# grizzly_bear.net
KiCad netlist of a schematic drawn in EAGLE
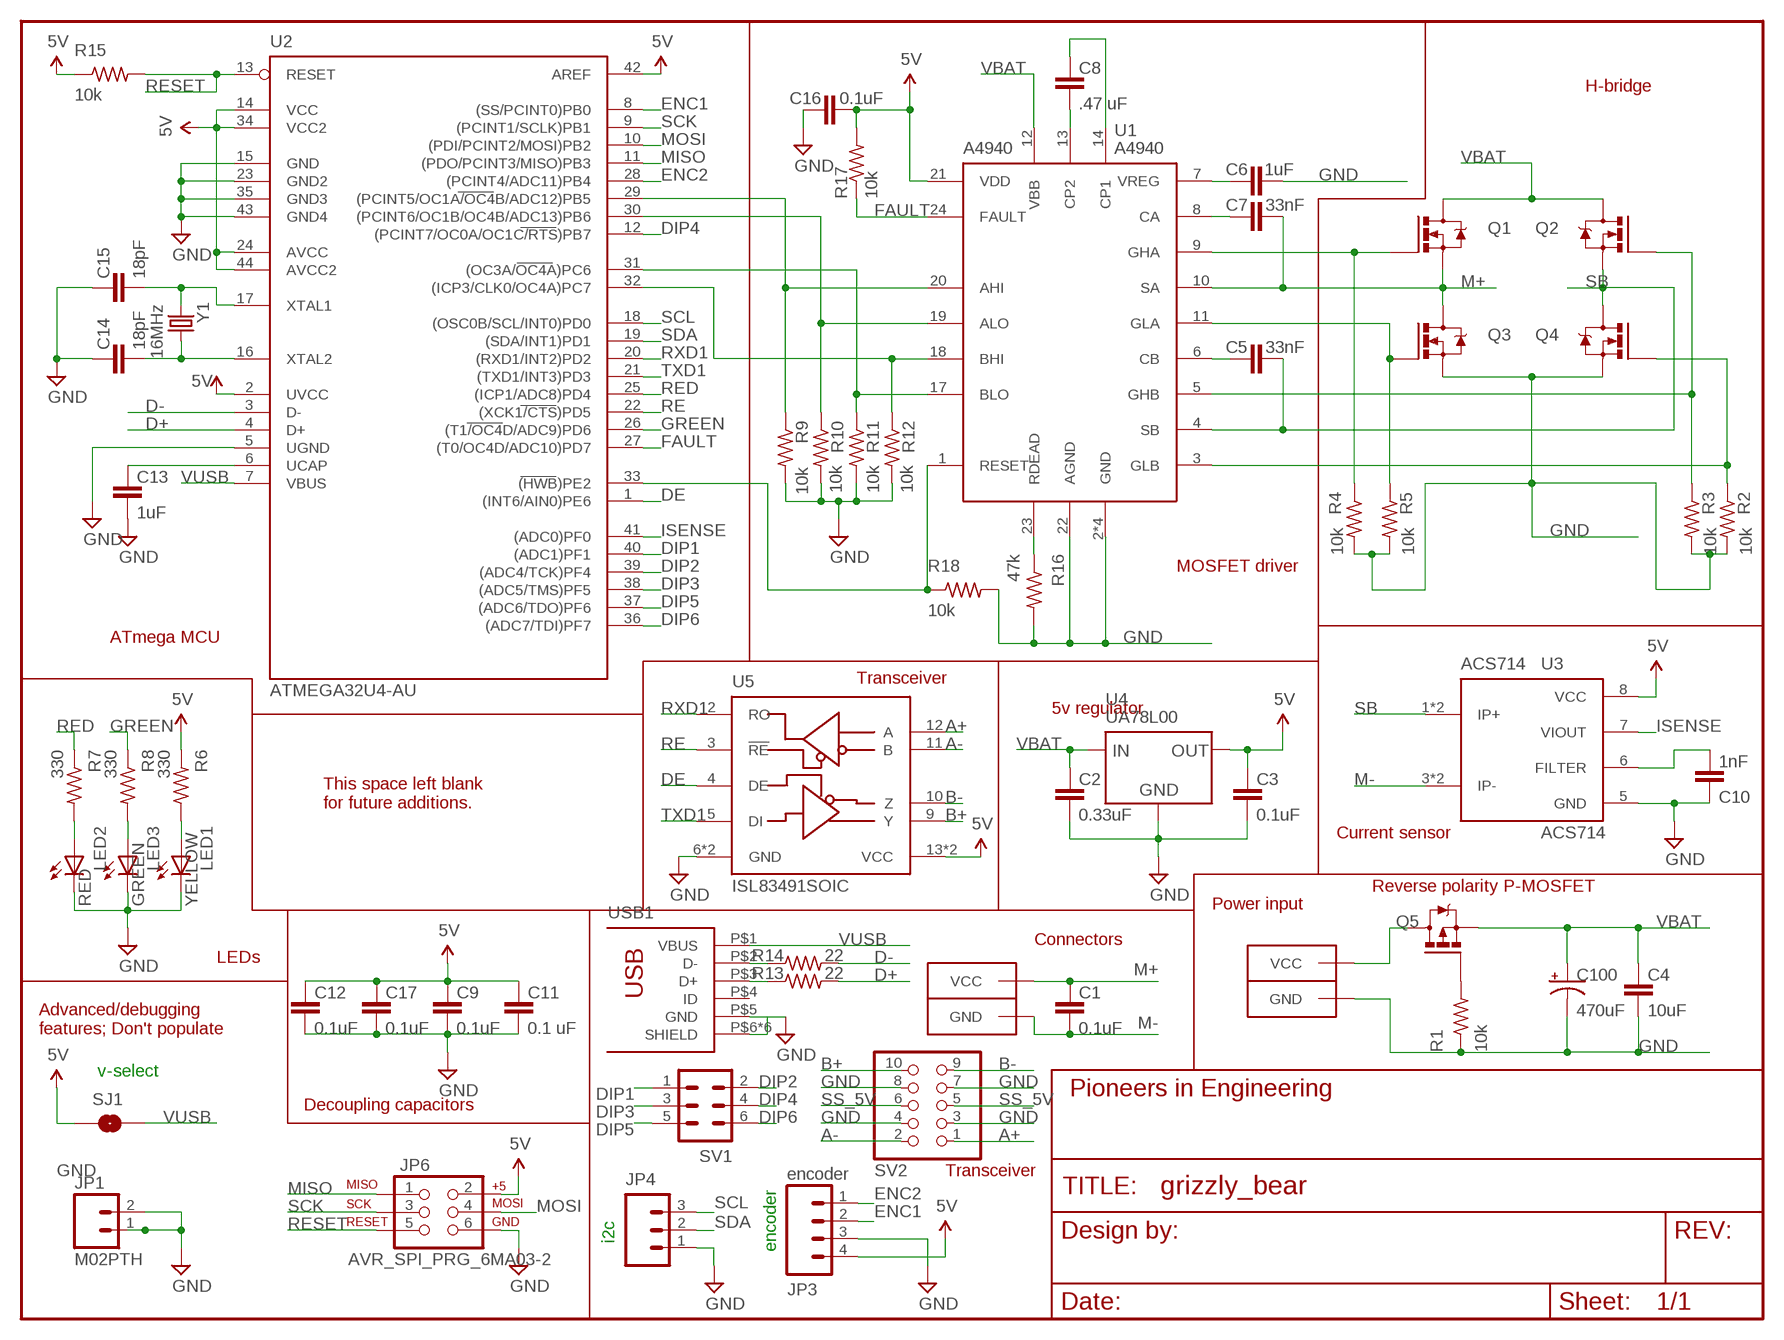
[diagram p0: schematic, sheet 1]

(export (version "E")
  (design (tool "Eeschema 10.0.6"))
  (components
    (comp (ref "C1")
      (value "0.1uF")
      (footprint "eagle-import:0603-CAP")
      (libsource (lib "eagle-import") (part "CAP0603-CAP"))
    )
    (comp (ref "C2")
      (value "0.33uF")
      (footprint "eagle-import:0603-CAP")
      (libsource (lib "eagle-import") (part "CAP0603-CAP"))
    )
    (comp (ref "C3")
      (value "0.1uF")
      (footprint "eagle-import:0603-CAP")
      (libsource (lib "eagle-import") (part "CAP0603-CAP"))
    )
    (comp (ref "C4")
      (value "10uF")
      (footprint "eagle-import:1206")
      (libsource (lib "eagle-import") (part "CAP1206"))
    )
    (comp (ref "C5")
      (value "33nF")
      (footprint "eagle-import:0603-CAP")
      (libsource (lib "eagle-import") (part "CAP0603-CAP"))
    )
    (comp (ref "C6")
      (value "1uF")
      (footprint "eagle-import:0603-CAP")
      (libsource (lib "eagle-import") (part "CAP0603-CAP"))
    )
    (comp (ref "C7")
      (value "33nF")
      (footprint "eagle-import:0603-CAP")
      (libsource (lib "eagle-import") (part "CAP0603-CAP"))
    )
    (comp (ref "C8")
      (value ".47 uF")
      (footprint "eagle-import:0603-CAP")
      (libsource (lib "eagle-import") (part "CAP0603-CAP"))
    )
    (comp (ref "C9")
      (value "0.1uF")
      (footprint "eagle-import:0603-CAP")
      (libsource (lib "eagle-import") (part "CAP0603-CAP"))
    )
    (comp (ref "C10")
      (value "1nF")
      (footprint "eagle-import:0603-CAP")
      (libsource (lib "eagle-import") (part "CAP0603-CAP"))
    )
    (comp (ref "C11")
      (value "0.1 uF")
      (footprint "eagle-import:0603-CAP")
      (libsource (lib "eagle-import") (part "CAP0603-CAP"))
    )
    (comp (ref "C12")
      (value "0.1uF")
      (footprint "eagle-import:0603-CAP")
      (libsource (lib "eagle-import") (part "CAP0603-CAP"))
    )
    (comp (ref "C13")
      (value "1uF")
      (footprint "eagle-import:0603-CAP")
      (libsource (lib "eagle-import") (part "CAP0603-CAP"))
    )
    (comp (ref "C14")
      (value "18pF")
      (footprint "eagle-import:0603-CAP")
      (libsource (lib "eagle-import") (part "CAP0603-CAP"))
    )
    (comp (ref "C15")
      (value "18pF")
      (footprint "eagle-import:0603-CAP")
      (libsource (lib "eagle-import") (part "CAP0603-CAP"))
    )
    (comp (ref "C16")
      (value "0.1uF")
      (footprint "eagle-import:0603-CAP")
      (libsource (lib "eagle-import") (part "CAP0603-CAP"))
    )
    (comp (ref "C17")
      (value "0.1uF")
      (footprint "eagle-import:0603-CAP")
      (libsource (lib "eagle-import") (part "CAP0603-CAP"))
    )
    (comp (ref "C100")
      (value "470uF")
      (footprint "eagle-import:PANASONIC_G")
      (libsource (lib "eagle-import") (part "CAP_POLG"))
    )
    (comp (ref "JP1")
      (value "M02PTH")
      (footprint "eagle-import:1X02")
      (libsource (lib "eagle-import") (part "M02PTH"))
    )
    (comp (ref "JP3")
      (value "encoder")
      (footprint "eagle-import:1X04-MTA")
      (libsource (lib "eagle-import") (part "M041X04-MTA"))
    )
    (comp (ref "JP4")
      (value "M031X03-MTA")
      (footprint "eagle-import:1X03-MTA")
      (libsource (lib "eagle-import") (part "M031X03-MTA"))
    )
    (comp (ref "JP6")
      (value "AVR_SPI_PRG_6MA03-2")
      (footprint "eagle-import:MA03-2")
      (libsource (lib "eagle-import") (part "AVR_SPI_PRG_6MA03-2"))
    )
    (comp (ref "LED1")
      (value "YELLOW")
      (footprint "eagle-import:LED-0805")
      (libsource (lib "eagle-import") (part "LED0805"))
    )
    (comp (ref "LED2")
      (value "RED")
      (footprint "eagle-import:LED-0805")
      (libsource (lib "eagle-import") (part "LED0805"))
    )
    (comp (ref "LED3")
      (value "GREEN")
      (footprint "eagle-import:LED-0805")
      (libsource (lib "eagle-import") (part "LED0805"))
    )
    (comp (ref "Q1")
      (value "PSMN4R0")
      (footprint "eagle-import:SOT669")
      (libsource (lib "eagle-import") (part "N-CHANNEL-MOSFETSOT669"))
    )
    (comp (ref "Q2")
      (value "PSMN4R0")
      (footprint "eagle-import:SOT669")
      (libsource (lib "eagle-import") (part "N-CHANNEL-MOSFETSOT669"))
    )
    (comp (ref "Q3")
      (value "PSMN4R0")
      (footprint "eagle-import:SOT669")
      (libsource (lib "eagle-import") (part "N-CHANNEL-MOSFETSOT669"))
    )
    (comp (ref "Q4")
      (value "PSMN4R0")
      (footprint "eagle-import:SOT669")
      (libsource (lib "eagle-import") (part "N-CHANNEL-MOSFETSOT669"))
    )
    (comp (ref "Q5")
      (value "IPD90P03P4L")
      (footprint "eagle-import:TO252")
      (libsource (lib "eagle-import") (part "P-CHANNEL-MOSFETTO252"))
    )
    (comp (ref "R1")
      (value "10k")
      (footprint "eagle-import:R0603")
      (libsource (lib "eagle-import") (part "R-US_R0603"))
    )
    (comp (ref "R2")
      (value "10k")
      (footprint "eagle-import:R0603")
      (libsource (lib "eagle-import") (part "R-US_R0603"))
    )
    (comp (ref "R3")
      (value "10k")
      (footprint "eagle-import:R0603")
      (libsource (lib "eagle-import") (part "R-US_R0603"))
    )
    (comp (ref "R4")
      (value "10k")
      (footprint "eagle-import:R0603")
      (libsource (lib "eagle-import") (part "R-US_R0603"))
    )
    (comp (ref "R5")
      (value "10k")
      (footprint "eagle-import:R0603")
      (libsource (lib "eagle-import") (part "R-US_R0603"))
    )
    (comp (ref "R6")
      (value "330")
      (footprint "eagle-import:R0603")
      (libsource (lib "eagle-import") (part "R-US_R0603"))
    )
    (comp (ref "R7")
      (value "330")
      (footprint "eagle-import:R0603")
      (libsource (lib "eagle-import") (part "R-US_R0603"))
    )
    (comp (ref "R8")
      (value "330")
      (footprint "eagle-import:R0603")
      (libsource (lib "eagle-import") (part "R-US_R0603"))
    )
    (comp (ref "R9")
      (value "10k")
      (footprint "eagle-import:R0603")
      (libsource (lib "eagle-import") (part "R-US_R0603"))
    )
    (comp (ref "R10")
      (value "10k")
      (footprint "eagle-import:R0603")
      (libsource (lib "eagle-import") (part "R-US_R0603"))
    )
    (comp (ref "R11")
      (value "10k")
      (footprint "eagle-import:R0603")
      (libsource (lib "eagle-import") (part "R-US_R0603"))
    )
    (comp (ref "R12")
      (value "10k")
      (footprint "eagle-import:R0603")
      (libsource (lib "eagle-import") (part "R-US_R0603"))
    )
    (comp (ref "R13")
      (value "22")
      (footprint "eagle-import:R0603")
      (libsource (lib "eagle-import") (part "R-US_R0603"))
    )
    (comp (ref "R14")
      (value "22")
      (footprint "eagle-import:R0603")
      (libsource (lib "eagle-import") (part "R-US_R0603"))
    )
    (comp (ref "R15")
      (value "10k")
      (footprint "eagle-import:R0603")
      (libsource (lib "eagle-import") (part "R-US_R0603"))
    )
    (comp (ref "R16")
      (value "47k")
      (footprint "eagle-import:R0603")
      (libsource (lib "eagle-import") (part "R-US_R0603"))
    )
    (comp (ref "R17")
      (value "10k")
      (footprint "eagle-import:R0603")
      (libsource (lib "eagle-import") (part "R-US_R0603"))
    )
    (comp (ref "R18")
      (value "10k")
      (footprint "eagle-import:R0603")
      (libsource (lib "eagle-import") (part "R-US_R0603"))
    )
    (comp (ref "SJ1")
      (value "SOLDERJUMPERNO")
      (footprint "eagle-import:SJ_2S-NO")
      (libsource (lib "eagle-import") (part "SOLDERJUMPERNO"))
    )
    (comp (ref "SV1")
      (value "MA03-2")
      (footprint "eagle-import:MA03-2")
      (libsource (lib "eagle-import") (part "MA03-2"))
    )
    (comp (ref "SV2")
      (value "SENSOR_CON_5PINPTH-SHROUDED")
      (footprint "eagle-import:2X5_SHROUDED")
      (libsource (lib "eagle-import") (part "SENSOR_CON_5PINPTH-SHROUDED"))
    )
    (comp (ref "U$18")
      (value "ANDERSONVERTICAL")
      (footprint "eagle-import:ANDERSON_VERTICAL")
      (libsource (lib "eagle-import") (part "ANDERSONVERTICAL"))
    )
    (comp (ref "U$19")
      (value "ANDERSONVERTICAL")
      (footprint "eagle-import:ANDERSON_VERTICAL")
      (libsource (lib "eagle-import") (part "ANDERSONVERTICAL"))
    )
    (comp (ref "U1")
      (value "A4940")
      (footprint "eagle-import:24-PIN_TSSOP")
      (libsource (lib "eagle-import") (part "A4940"))
    )
    (comp (ref "U2")
      (value "ATMEGA32U4-AU")
      (footprint "eagle-import:TQFP44")
      (libsource (lib "eagle-import") (part "ATMEGA32U4-AU"))
    )
    (comp (ref "U3")
      (value "ACS714")
      (footprint "eagle-import:8-PIN_SOIC")
      (libsource (lib "eagle-import") (part "ACS714"))
    )
    (comp (ref "U4")
      (value "UA78L00")
      (footprint "eagle-import:SOT-89-3")
      (libsource (lib "eagle-import") (part "UA78L00"))
    )
    (comp (ref "U5")
      (value "ISL83491SOIC")
      (footprint "eagle-import:SOIC14")
      (libsource (lib "eagle-import") (part "ISL83491SOIC"))
    )
    (comp (ref "USB1")
      (value "USB-OTGMICRO-AB")
      (footprint "eagle-import:USB-MICRO-AB")
      (libsource (lib "eagle-import") (part "USB-OTGMICRO-AB"))
    )
    (comp (ref "Y1")
      (value "16MHz")
      (footprint "eagle-import:HC49UP")
      (libsource (lib "eagle-import") (part "CRYSTALSMD"))
    )
  )
  (nets
    (net (code "1") (name "/A+") (class "Default")
      (node (ref "SV2") (pin "1") (pinfunction "1_1") (pintype "passive"))
      (node (ref "U5") (pin "12") (pinfunction "A_12") (pintype "bidirectional"))
    )
    (net (code "2") (name "/A-") (class "Default")
      (node (ref "SV2") (pin "2") (pinfunction "2_2") (pintype "passive"))
      (node (ref "U5") (pin "11") (pinfunction "B_11") (pintype "bidirectional"))
    )
    (net (code "3") (name "/B+") (class "Default")
      (node (ref "SV2") (pin "10") (pinfunction "10_10") (pintype "passive"))
      (node (ref "U5") (pin "9") (pinfunction "Y_9") (pintype "bidirectional"))
    )
    (net (code "4") (name "/B-") (class "Default")
      (node (ref "SV2") (pin "9") (pinfunction "9_9") (pintype "passive"))
      (node (ref "U5") (pin "10") (pinfunction "Z_10") (pintype "bidirectional"))
    )
    (net (code "5") (name "/D+") (class "Default")
      (node (ref "R13") (pin "2") (pinfunction "2_2") (pintype "passive"))
      (node (ref "U2") (pin "4") (pinfunction "D+_4") (pintype "bidirectional"))
    )
    (net (code "6") (name "/D-") (class "Default")
      (node (ref "R14") (pin "2") (pinfunction "2_2") (pintype "passive"))
      (node (ref "U2") (pin "3") (pinfunction "D-_3") (pintype "bidirectional"))
    )
    (net (code "7") (name "/DE") (class "Default")
      (node (ref "U2") (pin "1") (pinfunction "(INT6/AIN0)PE6_1") (pintype "bidirectional"))
      (node (ref "U5") (pin "4") (pinfunction "DE_4") (pintype "bidirectional"))
    )
    (net (code "8") (name "/DIP1") (class "Default")
      (node (ref "SV1") (pin "1") (pinfunction "1_1") (pintype "passive"))
      (node (ref "U2") (pin "40") (pinfunction "(ADC1)PF1_40") (pintype "bidirectional"))
    )
    (net (code "9") (name "/DIP2") (class "Default")
      (node (ref "SV1") (pin "2") (pinfunction "2_2") (pintype "passive"))
      (node (ref "U2") (pin "39") (pinfunction "(ADC4/TCK)PF4_39") (pintype "bidirectional"))
    )
    (net (code "10") (name "/DIP3") (class "Default")
      (node (ref "SV1") (pin "3") (pinfunction "3_3") (pintype "passive"))
      (node (ref "U2") (pin "38") (pinfunction "(ADC5/TMS)PF5_38") (pintype "bidirectional"))
    )
    (net (code "11") (name "/DIP4") (class "Default")
      (node (ref "SV1") (pin "4") (pinfunction "4_4") (pintype "passive"))
      (node (ref "U2") (pin "12") (pinfunction "(PCINT7/OC0A/OC1C/RTS)PB7_12") (pintype "bidirectional"))
    )
    (net (code "12") (name "/DIP5") (class "Default")
      (node (ref "SV1") (pin "5") (pinfunction "5_5") (pintype "passive"))
      (node (ref "U2") (pin "37") (pinfunction "(ADC6/TDO)PF6_37") (pintype "bidirectional"))
    )
    (net (code "13") (name "/DIP6") (class "Default")
      (node (ref "SV1") (pin "6") (pinfunction "6_6") (pintype "passive"))
      (node (ref "U2") (pin "36") (pinfunction "(ADC7/TDI)PF7_36") (pintype "bidirectional"))
    )
    (net (code "14") (name "/ENC1") (class "Default")
      (node (ref "JP3") (pin "2") (pinfunction "2_2") (pintype "passive"))
      (node (ref "U2") (pin "8") (pinfunction "(SS/PCINT0)PB0_8") (pintype "bidirectional"))
    )
    (net (code "15") (name "/ENC2") (class "Default")
      (node (ref "JP3") (pin "1") (pinfunction "1_1") (pintype "passive"))
      (node (ref "U2") (pin "28") (pinfunction "(PCINT4/ADC11)PB4_28") (pintype "bidirectional"))
    )
    (net (code "16") (name "/FAULT") (class "Default")
      (node (ref "R17") (pin "1") (pinfunction "1_1") (pintype "passive"))
      (node (ref "U1") (pin "24") (pinfunction "FAULT_24") (pintype "bidirectional"))
      (node (ref "U2") (pin "27") (pinfunction "(T0/OC4D/ADC10)PD7_27") (pintype "bidirectional"))
    )
    (net (code "17") (name "/GREEN") (class "Default")
      (node (ref "R8") (pin "1") (pinfunction "1_1") (pintype "passive"))
      (node (ref "U2") (pin "26") (pinfunction "(T1/OC4D/ADC9)PD6_26") (pintype "bidirectional"))
    )
    (net (code "18") (name "/ISENSE") (class "Default")
      (node (ref "U2") (pin "41") (pinfunction "(ADC0)PF0_41") (pintype "bidirectional"))
      (node (ref "U3") (pin "7") (pinfunction "VIOUT_7") (pintype "bidirectional"))
    )
    (net (code "19") (name "/M+") (class "Default")
      (node (ref "C1") (pin "1") (pinfunction "1_1") (pintype "passive"))
      (node (ref "C7") (pin "2") (pinfunction "2_2") (pintype "passive"))
      (node (ref "Q1") (pin "1") (pinfunction "S_1") (pintype "passive"))
      (node (ref "Q1") (pin "2") (pinfunction "S_2") (pintype "passive"))
      (node (ref "Q1") (pin "3") (pinfunction "S_3") (pintype "passive"))
      (node (ref "Q3") (pin "MB") (pinfunction "D_MB") (pintype "passive"))
      (node (ref "U$19") (pin "PIN2") (pinfunction "VCC_PIN2") (pintype "bidirectional"))
      (node (ref "U1") (pin "10") (pinfunction "SA_10") (pintype "bidirectional"))
    )
    (net (code "20") (name "/M-") (class "Default")
      (node (ref "C1") (pin "2") (pinfunction "2_2") (pintype "passive"))
      (node (ref "U$19") (pin "PIN1") (pinfunction "GND_PIN1") (pintype "bidirectional"))
      (node (ref "U3") (pin "3") (pinfunction "IP-_3") (pintype "bidirectional"))
      (node (ref "U3") (pin "4") (pinfunction "IP-_4") (pintype "bidirectional"))
    )
    (net (code "21") (name "/MISO") (class "Default")
      (node (ref "JP6") (pin "1") (pinfunction "1_1") (pintype "passive"))
      (node (ref "U2") (pin "11") (pinfunction "(PDO/PCINT3/MISO)PB3_11") (pintype "bidirectional"))
    )
    (net (code "22") (name "/MOSI") (class "Default")
      (node (ref "JP6") (pin "4") (pinfunction "4_4") (pintype "passive"))
      (node (ref "U2") (pin "10") (pinfunction "(PDI/PCINT2/MOSI)PB2_10") (pintype "bidirectional"))
    )
    (net (code "23") (name "/RE") (class "Default")
      (node (ref "U2") (pin "22") (pinfunction "(XCK1/CTS)PD5_22") (pintype "bidirectional"))
      (node (ref "U5") (pin "3") (pinfunction "~{RE}_3") (pintype "bidirectional"))
    )
    (net (code "24") (name "/RED") (class "Default")
      (node (ref "R7") (pin "1") (pinfunction "1_1") (pintype "passive"))
      (node (ref "U2") (pin "25") (pinfunction "(ICP1/ADC8)PD4_25") (pintype "bidirectional"))
    )
    (net (code "25") (name "/RESET") (class "Default")
      (node (ref "JP6") (pin "5") (pinfunction "5_5") (pintype "passive"))
      (node (ref "R15") (pin "2") (pinfunction "2_2") (pintype "passive"))
      (node (ref "U2") (pin "13") (pinfunction "RESET_13") (pintype "bidirectional"))
    )
    (net (code "26") (name "/RXD1") (class "Default")
      (node (ref "U2") (pin "20") (pinfunction "(RXD1/INT2)PD2_20") (pintype "bidirectional"))
      (node (ref "U5") (pin "2") (pinfunction "RO_2") (pintype "bidirectional"))
    )
    (net (code "27") (name "/SB") (class "Default")
      (node (ref "C5") (pin "1") (pinfunction "1_1") (pintype "passive"))
      (node (ref "Q2") (pin "1") (pinfunction "S_1") (pintype "passive"))
      (node (ref "Q2") (pin "2") (pinfunction "S_2") (pintype "passive"))
      (node (ref "Q2") (pin "3") (pinfunction "S_3") (pintype "passive"))
      (node (ref "Q4") (pin "MB") (pinfunction "D_MB") (pintype "passive"))
      (node (ref "U1") (pin "4") (pinfunction "SB_4") (pintype "bidirectional"))
      (node (ref "U3") (pin "1") (pinfunction "IP+_1") (pintype "bidirectional"))
      (node (ref "U3") (pin "2") (pinfunction "IP+_2") (pintype "bidirectional"))
    )
    (net (code "28") (name "/SCK") (class "Default")
      (node (ref "JP6") (pin "3") (pinfunction "3_3") (pintype "passive"))
      (node (ref "U2") (pin "9") (pinfunction "(PCINT1/SCLK)PB1_9") (pintype "bidirectional"))
    )
    (net (code "29") (name "/SCL") (class "Default")
      (node (ref "JP4") (pin "3") (pinfunction "3_3") (pintype "passive"))
      (node (ref "U2") (pin "18") (pinfunction "(OSC0B/SCL/INT0)PD0_18") (pintype "bidirectional"))
    )
    (net (code "30") (name "/SDA") (class "Default")
      (node (ref "JP4") (pin "2") (pinfunction "2_2") (pintype "passive"))
      (node (ref "U2") (pin "19") (pinfunction "(SDA/INT1)PD1_19") (pintype "bidirectional"))
    )
    (net (code "31") (name "/SS_5V") (class "Default")
      (node (ref "SV2") (pin "5") (pinfunction "5_5") (pintype "passive"))
      (node (ref "SV2") (pin "6") (pinfunction "6_6") (pintype "passive"))
    )
    (net (code "32") (name "/TXD1") (class "Default")
      (node (ref "U2") (pin "21") (pinfunction "(TXD1/INT3)PD3_21") (pintype "bidirectional"))
      (node (ref "U5") (pin "5") (pinfunction "DI_5") (pintype "bidirectional"))
    )
    (net (code "33") (name "/VBAT") (class "Default")
      (node (ref "C100") (pin "+") (pinfunction "+_+") (pintype "passive"))
      (node (ref "C2") (pin "1") (pinfunction "1_1") (pintype "passive"))
      (node (ref "C4") (pin "2") (pinfunction "2_2") (pintype "passive"))
      (node (ref "Q1") (pin "MB") (pinfunction "D_MB") (pintype "passive"))
      (node (ref "Q2") (pin "MB") (pinfunction "D_MB") (pintype "passive"))
      (node (ref "Q5") (pin "2") (pinfunction "S_2") (pintype "passive"))
      (node (ref "U1") (pin "12") (pinfunction "VBB_12") (pintype "bidirectional"))
      (node (ref "U4") (pin "INPUT") (pinfunction "IN_INPUT") (pintype "bidirectional"))
    )
    (net (code "34") (name "/VUSB") (class "Default")
      (node (ref "SJ1") (pin "2") (pinfunction "2_2") (pintype "passive"))
      (node (ref "U2") (pin "7") (pinfunction "VBUS_7") (pintype "bidirectional"))
      (node (ref "USB1") (pin "P$1") (pinfunction "VBUS_P$1") (pintype "bidirectional"))
    )
    (net (code "35") (name "5V") (class "Default")
      (node (ref "C11") (pin "2") (pinfunction "2_2") (pintype "passive"))
      (node (ref "C12") (pin "1") (pinfunction "1_1") (pintype "passive"))
      (node (ref "C16") (pin "1") (pinfunction "1_1") (pintype "passive"))
      (node (ref "C17") (pin "1") (pinfunction "1_1") (pintype "passive"))
      (node (ref "C3") (pin "1") (pinfunction "1_1") (pintype "passive"))
      (node (ref "C9") (pin "1") (pinfunction "1_1") (pintype "passive"))
      (node (ref "JP3") (pin "4") (pinfunction "4_4") (pintype "passive"))
      (node (ref "JP6") (pin "2") (pinfunction "2_2") (pintype "passive"))
      (node (ref "R15") (pin "1") (pinfunction "1_1") (pintype "passive"))
      (node (ref "R17") (pin "2") (pinfunction "2_2") (pintype "passive"))
      (node (ref "R6") (pin "2") (pinfunction "2_2") (pintype "passive"))
      (node (ref "SJ1") (pin "1") (pinfunction "1_1") (pintype "passive"))
      (node (ref "U1") (pin "21") (pinfunction "VDD_21") (pintype "bidirectional"))
      (node (ref "U2") (pin "14") (pinfunction "VCC_14") (pintype "bidirectional"))
      (node (ref "U2") (pin "2") (pinfunction "UVCC_2") (pintype "bidirectional"))
      (node (ref "U2") (pin "24") (pinfunction "AVCC_24") (pintype "bidirectional"))
      (node (ref "U2") (pin "34") (pinfunction "VCC2_34") (pintype "bidirectional"))
      (node (ref "U2") (pin "42") (pinfunction "AREF_42") (pintype "bidirectional"))
      (node (ref "U2") (pin "44") (pinfunction "AVCC2_44") (pintype "bidirectional"))
      (node (ref "U3") (pin "8") (pinfunction "VCC_8") (pintype "bidirectional"))
      (node (ref "U4") (pin "OUTPUT") (pinfunction "OUT_OUTPUT") (pintype "bidirectional"))
      (node (ref "U5") (pin "13") (pinfunction "VCC_13") (pintype "bidirectional"))
      (node (ref "U5") (pin "14") (pinfunction "VCC_14") (pintype "bidirectional"))
    )
    (net (code "36") (name "GND") (class "Default")
      (node (ref "C10") (pin "1") (pinfunction "1_1") (pintype "passive"))
      (node (ref "C100") (pin "-") (pinfunction "-_-") (pintype "passive"))
      (node (ref "C11") (pin "1") (pinfunction "1_1") (pintype "passive"))
      (node (ref "C12") (pin "2") (pinfunction "2_2") (pintype "passive"))
      (node (ref "C13") (pin "2") (pinfunction "2_2") (pintype "passive"))
      (node (ref "C14") (pin "1") (pinfunction "1_1") (pintype "passive"))
      (node (ref "C15") (pin "1") (pinfunction "1_1") (pintype "passive"))
      (node (ref "C16") (pin "2") (pinfunction "2_2") (pintype "passive"))
      (node (ref "C17") (pin "2") (pinfunction "2_2") (pintype "passive"))
      (node (ref "C2") (pin "2") (pinfunction "2_2") (pintype "passive"))
      (node (ref "C3") (pin "2") (pinfunction "2_2") (pintype "passive"))
      (node (ref "C4") (pin "1") (pinfunction "1_1") (pintype "passive"))
      (node (ref "C6") (pin "2") (pinfunction "2_2") (pintype "passive"))
      (node (ref "C9") (pin "2") (pinfunction "2_2") (pintype "passive"))
      (node (ref "JP1") (pin "1") (pinfunction "1_1") (pintype "passive"))
      (node (ref "JP1") (pin "2") (pinfunction "2_2") (pintype "passive"))
      (node (ref "JP3") (pin "3") (pinfunction "3_3") (pintype "passive"))
      (node (ref "JP4") (pin "1") (pinfunction "1_1") (pintype "passive"))
      (node (ref "JP6") (pin "6") (pinfunction "6_6") (pintype "passive"))
      (node (ref "LED1") (pin "C") (pinfunction "C_C") (pintype "passive"))
      (node (ref "LED2") (pin "C") (pinfunction "C_C") (pintype "passive"))
      (node (ref "LED3") (pin "C") (pinfunction "C_C") (pintype "passive"))
      (node (ref "Q3") (pin "1") (pinfunction "S_1") (pintype "passive"))
      (node (ref "Q3") (pin "2") (pinfunction "S_2") (pintype "passive"))
      (node (ref "Q3") (pin "3") (pinfunction "S_3") (pintype "passive"))
      (node (ref "Q4") (pin "1") (pinfunction "S_1") (pintype "passive"))
      (node (ref "Q4") (pin "2") (pinfunction "S_2") (pintype "passive"))
      (node (ref "Q4") (pin "3") (pinfunction "S_3") (pintype "passive"))
      (node (ref "R1") (pin "1") (pinfunction "1_1") (pintype "passive"))
      (node (ref "R10") (pin "2") (pinfunction "2_2") (pintype "passive"))
      (node (ref "R11") (pin "2") (pinfunction "2_2") (pintype "passive"))
      (node (ref "R12") (pin "2") (pinfunction "2_2") (pintype "passive"))
      (node (ref "R16") (pin "2") (pinfunction "2_2") (pintype "passive"))
      (node (ref "R18") (pin "2") (pinfunction "2_2") (pintype "passive"))
      (node (ref "R2") (pin "2") (pinfunction "2_2") (pintype "passive"))
      (node (ref "R3") (pin "2") (pinfunction "2_2") (pintype "passive"))
      (node (ref "R4") (pin "2") (pinfunction "2_2") (pintype "passive"))
      (node (ref "R5") (pin "2") (pinfunction "2_2") (pintype "passive"))
      (node (ref "R9") (pin "2") (pinfunction "2_2") (pintype "passive"))
      (node (ref "SV2") (pin "3") (pinfunction "3_3") (pintype "passive"))
      (node (ref "SV2") (pin "4") (pinfunction "4_4") (pintype "passive"))
      (node (ref "SV2") (pin "7") (pinfunction "7_7") (pintype "passive"))
      (node (ref "SV2") (pin "8") (pinfunction "8_8") (pintype "passive"))
      (node (ref "U$18") (pin "PIN1") (pinfunction "GND_PIN1") (pintype "bidirectional"))
      (node (ref "U1") (pin "15") (pinfunction "GND_15") (pintype "bidirectional"))
      (node (ref "U1") (pin "16") (pinfunction "GND_16") (pintype "bidirectional"))
      (node (ref "U1") (pin "2") (pinfunction "GND_2") (pintype "bidirectional"))
      (node (ref "U1") (pin "22") (pinfunction "AGND_22") (pintype "bidirectional"))
      (node (ref "U1") (pin "PAD") (pinfunction "GND_PAD") (pintype "bidirectional"))
      (node (ref "U2") (pin "15") (pinfunction "GND_15") (pintype "bidirectional"))
      (node (ref "U2") (pin "23") (pinfunction "GND2_23") (pintype "bidirectional"))
      (node (ref "U2") (pin "35") (pinfunction "GND3_35") (pintype "bidirectional"))
      (node (ref "U2") (pin "43") (pinfunction "GND4_43") (pintype "bidirectional"))
      (node (ref "U2") (pin "5") (pinfunction "UGND_5") (pintype "bidirectional"))
      (node (ref "U3") (pin "5") (pinfunction "GND_5") (pintype "bidirectional"))
      (node (ref "U4") (pin "COMMON") (pinfunction "GND_COMMON") (pintype "bidirectional"))
      (node (ref "U5") (pin "6") (pinfunction "GND_6") (pintype "bidirectional"))
      (node (ref "U5") (pin "7") (pinfunction "GND_7") (pintype "bidirectional"))
      (node (ref "USB1") (pin "P$10") (pinfunction "SHIELD_P$10") (pintype "bidirectional"))
      (node (ref "USB1") (pin "P$11") (pinfunction "SHIELD_P$11") (pintype "bidirectional"))
      (node (ref "USB1") (pin "P$5") (pinfunction "GND_P$5") (pintype "bidirectional"))
      (node (ref "USB1") (pin "P$6") (pinfunction "SHIELD_P$6") (pintype "bidirectional"))
      (node (ref "USB1") (pin "P$7") (pinfunction "SHIELD_P$7") (pintype "bidirectional"))
      (node (ref "USB1") (pin "P$8") (pinfunction "SHIELD_P$8") (pintype "bidirectional"))
      (node (ref "USB1") (pin "P$9") (pinfunction "SHIELD_P$9") (pintype "bidirectional"))
    )
    (net (code "37") (name "Net-(LED1-PadA)") (class "Default")
      (node (ref "LED1") (pin "A") (pinfunction "A_A") (pintype "passive"))
      (node (ref "R6") (pin "1") (pinfunction "1_1") (pintype "passive"))
    )
    (net (code "38") (name "Net-(LED2-PadA)") (class "Default")
      (node (ref "LED2") (pin "A") (pinfunction "A_A") (pintype "passive"))
      (node (ref "R7") (pin "2") (pinfunction "2_2") (pintype "passive"))
    )
    (net (code "39") (name "Net-(LED3-PadA)") (class "Default")
      (node (ref "LED3") (pin "A") (pinfunction "A_A") (pintype "passive"))
      (node (ref "R8") (pin "2") (pinfunction "2_2") (pintype "passive"))
    )
    (net (code "40") (name "Net-(Q1-G)") (class "Default")
      (node (ref "Q1") (pin "4") (pinfunction "G_4") (pintype "passive"))
      (node (ref "R4") (pin "1") (pinfunction "1_1") (pintype "passive"))
      (node (ref "U1") (pin "9") (pinfunction "GHA_9") (pintype "bidirectional"))
    )
    (net (code "41") (name "Net-(Q2-G)") (class "Default")
      (node (ref "Q2") (pin "4") (pinfunction "G_4") (pintype "passive"))
      (node (ref "R3") (pin "1") (pinfunction "1_1") (pintype "passive"))
      (node (ref "U1") (pin "5") (pinfunction "GHB_5") (pintype "bidirectional"))
    )
    (net (code "42") (name "Net-(Q3-G)") (class "Default")
      (node (ref "Q3") (pin "4") (pinfunction "G_4") (pintype "passive"))
      (node (ref "R5") (pin "1") (pinfunction "1_1") (pintype "passive"))
      (node (ref "U1") (pin "11") (pinfunction "GLA_11") (pintype "bidirectional"))
    )
    (net (code "43") (name "Net-(Q4-G)") (class "Default")
      (node (ref "Q4") (pin "4") (pinfunction "G_4") (pintype "passive"))
      (node (ref "R2") (pin "1") (pinfunction "1_1") (pintype "passive"))
      (node (ref "U1") (pin "3") (pinfunction "GLB_3") (pintype "bidirectional"))
    )
    (net (code "44") (name "Net-(Q5-D)") (class "Default")
      (node (ref "Q5") (pin "3") (pinfunction "D_3") (pintype "passive"))
      (node (ref "U$18") (pin "PIN2") (pinfunction "VCC_PIN2") (pintype "bidirectional"))
    )
    (net (code "45") (name "Net-(Q5-G)") (class "Default")
      (node (ref "Q5") (pin "1") (pinfunction "G_1") (pintype "passive"))
      (node (ref "R1") (pin "2") (pinfunction "2_2") (pintype "passive"))
    )
    (net (code "46") (name "Net-(U1-AHI)") (class "Default")
      (node (ref "R9") (pin "1") (pinfunction "1_1") (pintype "passive"))
      (node (ref "U1") (pin "20") (pinfunction "AHI_20") (pintype "bidirectional"))
      (node (ref "U2") (pin "29") (pinfunction "(PCINT5/OC1A/OC4B/ADC12)PB5_29") (pintype "bidirectional"))
    )
    (net (code "47") (name "Net-(U1-ALO)") (class "Default")
      (node (ref "R10") (pin "1") (pinfunction "1_1") (pintype "passive"))
      (node (ref "U1") (pin "19") (pinfunction "ALO_19") (pintype "bidirectional"))
      (node (ref "U2") (pin "30") (pinfunction "(PCINT6/OC1B/OC4B/ADC13)PB6_30") (pintype "bidirectional"))
    )
    (net (code "48") (name "Net-(U1-BHI)") (class "Default")
      (node (ref "R12") (pin "1") (pinfunction "1_1") (pintype "passive"))
      (node (ref "U1") (pin "18") (pinfunction "BHI_18") (pintype "bidirectional"))
      (node (ref "U2") (pin "32") (pinfunction "(ICP3/CLK0/OC4A)PC7_32") (pintype "bidirectional"))
    )
    (net (code "49") (name "Net-(U1-BLO)") (class "Default")
      (node (ref "R11") (pin "1") (pinfunction "1_1") (pintype "passive"))
      (node (ref "U1") (pin "17") (pinfunction "BLO_17") (pintype "bidirectional"))
      (node (ref "U2") (pin "31") (pinfunction "(OC3A/OC4A)PC6_31") (pintype "bidirectional"))
    )
    (net (code "50") (name "Net-(U1-CA)") (class "Default")
      (node (ref "C7") (pin "1") (pinfunction "1_1") (pintype "passive"))
      (node (ref "U1") (pin "8") (pinfunction "CA_8") (pintype "bidirectional"))
    )
    (net (code "51") (name "Net-(U1-CB)") (class "Default")
      (node (ref "C5") (pin "2") (pinfunction "2_2") (pintype "passive"))
      (node (ref "U1") (pin "6") (pinfunction "CB_6") (pintype "bidirectional"))
    )
    (net (code "52") (name "Net-(U1-CP1)") (class "Default")
      (node (ref "C8") (pin "1") (pinfunction "1_1") (pintype "passive"))
      (node (ref "U1") (pin "14") (pinfunction "CP1_14") (pintype "bidirectional"))
    )
    (net (code "53") (name "Net-(U1-CP2)") (class "Default")
      (node (ref "C8") (pin "2") (pinfunction "2_2") (pintype "passive"))
      (node (ref "U1") (pin "13") (pinfunction "CP2_13") (pintype "bidirectional"))
    )
    (net (code "54") (name "Net-(U1-RDEAD)") (class "Default")
      (node (ref "R16") (pin "1") (pinfunction "1_1") (pintype "passive"))
      (node (ref "U1") (pin "23") (pinfunction "RDEAD_23") (pintype "bidirectional"))
    )
    (net (code "55") (name "Net-(U1-RESET)") (class "Default")
      (node (ref "R18") (pin "1") (pinfunction "1_1") (pintype "passive"))
      (node (ref "U1") (pin "1") (pinfunction "RESET_1") (pintype "bidirectional"))
      (node (ref "U2") (pin "33") (pinfunction "(HWB)PE2_33") (pintype "bidirectional"))
    )
    (net (code "56") (name "Net-(U1-VREG)") (class "Default")
      (node (ref "C6") (pin "1") (pinfunction "1_1") (pintype "passive"))
      (node (ref "U1") (pin "7") (pinfunction "VREG_7") (pintype "bidirectional"))
    )
    (net (code "57") (name "Net-(U2-UCAP)") (class "Default")
      (node (ref "C13") (pin "1") (pinfunction "1_1") (pintype "passive"))
      (node (ref "U2") (pin "6") (pinfunction "UCAP_6") (pintype "bidirectional"))
    )
    (net (code "58") (name "Net-(U2-XTAL1)") (class "Default")
      (node (ref "C15") (pin "2") (pinfunction "2_2") (pintype "passive"))
      (node (ref "U2") (pin "17") (pinfunction "XTAL1_17") (pintype "bidirectional"))
      (node (ref "Y1") (pin "2") (pinfunction "2_2") (pintype "passive"))
    )
    (net (code "59") (name "Net-(U2-XTAL2)") (class "Default")
      (node (ref "C14") (pin "2") (pinfunction "2_2") (pintype "passive"))
      (node (ref "U2") (pin "16") (pinfunction "XTAL2_16") (pintype "bidirectional"))
      (node (ref "Y1") (pin "1") (pinfunction "1_1") (pintype "passive"))
    )
    (net (code "60") (name "Net-(U3-FILTER)") (class "Default")
      (node (ref "C10") (pin "2") (pinfunction "2_2") (pintype "passive"))
      (node (ref "U3") (pin "6") (pinfunction "FILTER_6") (pintype "bidirectional"))
    )
    (net (code "61") (name "Net-(USB1-D+)") (class "Default")
      (node (ref "R13") (pin "1") (pinfunction "1_1") (pintype "passive"))
      (node (ref "USB1") (pin "P$3") (pinfunction "D+_P$3") (pintype "bidirectional"))
    )
    (net (code "62") (name "Net-(USB1-D-)") (class "Default")
      (node (ref "R14") (pin "1") (pinfunction "1_1") (pintype "passive"))
      (node (ref "USB1") (pin "P$2") (pinfunction "D-_P$2") (pintype "bidirectional"))
    )
    (net (code "63") (name "unconnected-(USB1-ID-PadP$4)") (class "Default")
      (node (ref "USB1") (pin "P$4") (pinfunction "ID_P$4") (pintype "bidirectional"))
    )
  )
)
